# SD_CARD.net
KiCad netlist of a schematic drawn in Altium Designer
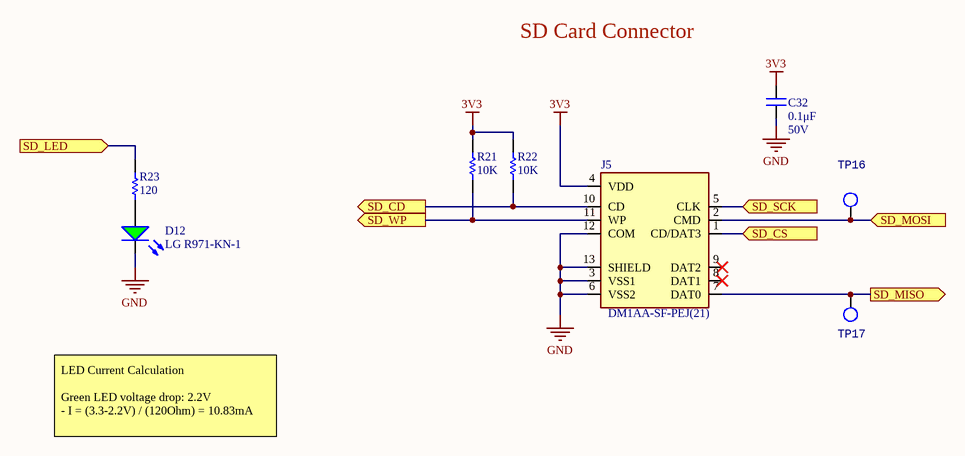
[diagram p0: SD_CARD.SchDoc]

(export (version "E")
  (design (tool "Eeschema 10.0.6"))
  (components
    (comp (ref "C32")
      (value "0.1μF")
      (footprint "CAP2012")
      (description "CAP CER 0.1UF 50V X7R 0805")
      (fields
        (field (name "TOLERANCE") "10%")
        (field (name "VOLTAGE RATING") "50V")
        (field (name "Comment") "CAP_0.1uF_50V_0805")
      )
      (libsource (lib "UWRT_Schematic_Library_2020") (part "CAP_0.1uF_50V_0805"))
    )
    (comp (ref "D12")
      (value "LG R971-KN-1")
      (footprint "LED_0805_GREEN")
      (description "LED GREEN DIFFUSED 0805 SMD")
      (libsource (lib "UWRT_Schematic_Library_2020") (part "DIO_LED_G"))
    )
    (comp (ref "J5")
      (value "SD_CARD_CON")
      (footprint "HRS_DM1AA-SF-PEJ(21)")
      (description "CONN SD CARD PUSH-PUSH R/A SMD")
      (fields (field (name "MANUFACTURER PART NUMBER 1") "DM1AA-SF-PEJ(21)"))
      (libsource (lib "UWRT_Schematic_Library_2020") (part "SD_CARD_CON"))
    )
    (comp (ref "R21")
      (value "10K")
      (footprint "RESC0603(1608)_N")
      (description "RES SMD 10K OHM 5% 1/10W 0603")
      (fields (field (name "TOLERANCE") "5%") (field (name "Comment") "RES_10K_0603"))
      (libsource (lib "UWRT_Schematic_Library_2020") (part "RES_10K_0603"))
    )
    (comp (ref "R22")
      (value "10K")
      (footprint "RESC0603(1608)_N")
      (description "RES SMD 10K OHM 5% 1/10W 0603")
      (fields (field (name "TOLERANCE") "5%") (field (name "Comment") "RES_10K_0603"))
      (libsource (lib "UWRT_Schematic_Library_2020") (part "RES_10K_0603"))
    )
    (comp (ref "R23")
      (value "120")
      (footprint "RESC0603(1608)_N")
      (description "RES SMD 120 OHM 5% 1/10W 0603")
      (fields (field (name "TOLERANCE") "5%") (field (name "Comment") "RES_120R_0603"))
      (libsource (lib "UWRT_Schematic_Library_2020") (part "RES_120R_0603"))
    )
    (comp (ref "TP16")
      (value "TESTPOINT_LOOP")
      (footprint "TESTPOINT_LOOP")
      (description "PC TEST POINT MINIATURE WHITE")
      (libsource (lib "UWRT_Schematic_Library_2020") (part "TESTPOINT_LOOP"))
    )
    (comp (ref "TP17")
      (value "TESTPOINT_LOOP")
      (footprint "TESTPOINT_LOOP")
      (description "PC TEST POINT MINIATURE WHITE")
      (libsource (lib "UWRT_Schematic_Library_2020") (part "TESTPOINT_LOOP"))
    )
  )
  (nets
    (net (code "1") (name "/SD_CD") (class "Default")
      (node (ref "J5") (pin "10") (pinfunction "CD_10") (pintype "passive"))
      (node (ref "R22") (pin "1") (pinfunction "1_1") (pintype "passive"))
    )
    (net (code "2") (name "/SD_CS") (class "Default")
      (node (ref "J5") (pin "1") (pinfunction "CD/DAT3_1") (pintype "passive"))
    )
    (net (code "3") (name "/SD_LED") (class "Default")
      (node (ref "R23") (pin "1") (pinfunction "1_1") (pintype "passive"))
    )
    (net (code "4") (name "/SD_MISO") (class "Default")
      (node (ref "J5") (pin "7") (pinfunction "DAT0_7") (pintype "passive"))
      (node (ref "TP17") (pin "1") (pintype "passive"))
    )
    (net (code "5") (name "/SD_MOSI") (class "Default")
      (node (ref "J5") (pin "2") (pinfunction "CMD_2") (pintype "passive"))
      (node (ref "TP16") (pin "1") (pintype "passive"))
    )
    (net (code "6") (name "/SD_SCK") (class "Default")
      (node (ref "J5") (pin "5") (pinfunction "CLK_5") (pintype "passive"))
    )
    (net (code "7") (name "/SD_WP") (class "Default")
      (node (ref "J5") (pin "11") (pinfunction "WP_11") (pintype "passive"))
      (node (ref "R21") (pin "1") (pinfunction "1_1") (pintype "passive"))
    )
    (net (code "8") (name "3V3") (class "Default")
      (node (ref "C32") (pin "2") (pinfunction "2_2") (pintype "passive"))
      (node (ref "J5") (pin "4") (pinfunction "VDD_4") (pintype "power_in"))
      (node (ref "R21") (pin "2") (pinfunction "2_2") (pintype "passive"))
      (node (ref "R22") (pin "2") (pinfunction "2_2") (pintype "passive"))
    )
    (net (code "9") (name "GND") (class "Default")
      (node (ref "C32") (pin "1") (pinfunction "1_1") (pintype "passive"))
      (node (ref "D12") (pin "2") (pinfunction "K_2") (pintype "passive"))
      (node (ref "J5") (pin "12") (pinfunction "COM_12") (pintype "passive"))
      (node (ref "J5") (pin "13") (pinfunction "SHIELD_13") (pintype "passive"))
      (node (ref "J5") (pin "3") (pinfunction "VSS1_3") (pintype "power_in"))
      (node (ref "J5") (pin "6") (pinfunction "VSS2_6") (pintype "power_in"))
    )
    (net (code "10") (name "Net-(D12-A)") (class "Default")
      (node (ref "D12") (pin "1") (pinfunction "A_1") (pintype "passive"))
      (node (ref "R23") (pin "2") (pinfunction "2_2") (pintype "passive"))
    )
    (net (code "11") (name "unconnected-(J5-DAT1-Pad8)") (class "Default")
      (node (ref "J5") (pin "8") (pinfunction "DAT1_8") (pintype "passive+no_connect"))
    )
    (net (code "12") (name "unconnected-(J5-DAT2-Pad9)") (class "Default")
      (node (ref "J5") (pin "9") (pinfunction "DAT2_9") (pintype "passive+no_connect"))
    )
  )
)
